# Yitran_IT900_Hutschiene_1_7.net
KiCad netlist of a schematic drawn in EAGLE
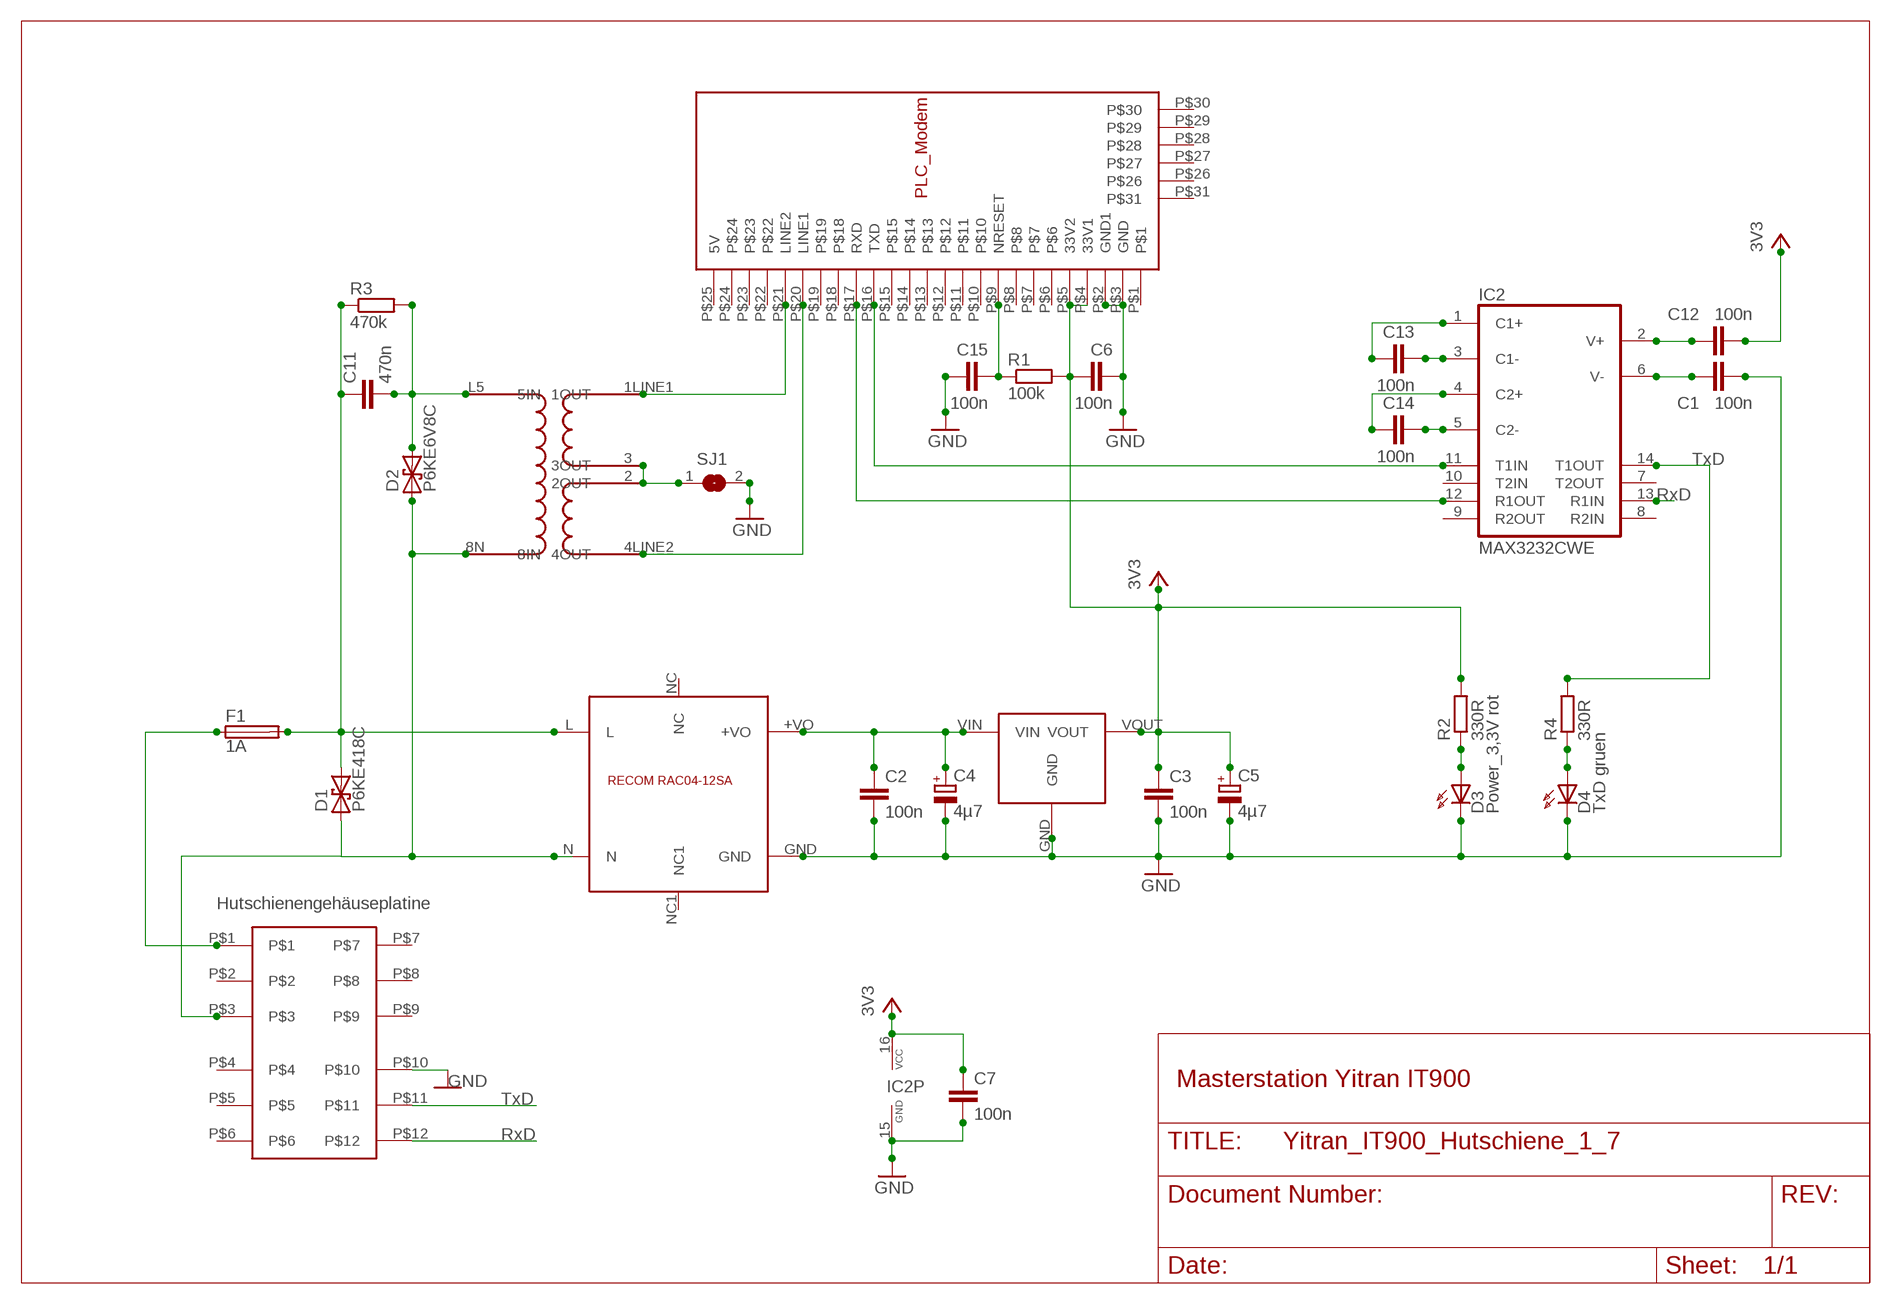
[diagram p0: schematic, sheet 1]

(export (version "E")
  (design (tool "Eeschema 10.0.6"))
  (components
    (comp (ref "C1")
      (value "100n")
      (footprint "eagle-import:C1206K")
      (libsource (lib "eagle-import") (part "C-EUC1206K"))
    )
    (comp (ref "C2")
      (value "100n")
      (footprint "eagle-import:C1206K")
      (libsource (lib "eagle-import") (part "C-EUC1206K"))
    )
    (comp (ref "C3")
      (value "100n")
      (footprint "eagle-import:C1206K")
      (libsource (lib "eagle-import") (part "C-EUC1206K"))
    )
    (comp (ref "C4")
      (value "4µ7")
      (footprint "eagle-import:E2,5-5")
      (libsource (lib "eagle-import") (part "CPOL-EUE2.5-5"))
    )
    (comp (ref "C5")
      (value "4µ7")
      (footprint "eagle-import:E2,5-5")
      (libsource (lib "eagle-import") (part "CPOL-EUE2.5-5"))
    )
    (comp (ref "C6")
      (value "100n")
      (footprint "eagle-import:C1206K")
      (libsource (lib "eagle-import") (part "C-EUC1206K"))
    )
    (comp (ref "C7")
      (value "100n")
      (footprint "eagle-import:C1206K")
      (libsource (lib "eagle-import") (part "C-EUC1206K"))
    )
    (comp (ref "C11")
      (value "470n")
      (footprint "eagle-import:C150-091X182")
      (libsource (lib "eagle-import") (part "C-EU150-091X182"))
    )
    (comp (ref "C12")
      (value "100n")
      (footprint "eagle-import:C1206K")
      (libsource (lib "eagle-import") (part "C-EUC1206K"))
    )
    (comp (ref "C13")
      (value "100n")
      (footprint "eagle-import:C1206K")
      (libsource (lib "eagle-import") (part "C-EUC1206K"))
    )
    (comp (ref "C14")
      (value "100n")
      (footprint "eagle-import:C1206K")
      (libsource (lib "eagle-import") (part "C-EUC1206K"))
    )
    (comp (ref "C15")
      (value "100n")
      (footprint "eagle-import:C1206K")
      (libsource (lib "eagle-import") (part "C-EUC1206K"))
    )
    (comp (ref "D1")
      (value "P6KE418C")
      (footprint "eagle-import:CB417-15")
      (libsource (lib "eagle-import") (part "P6KEXXC"))
    )
    (comp (ref "D2")
      (value "P6KE6V8C")
      (footprint "eagle-import:CB417-15")
      (libsource (lib "eagle-import") (part "P6KEXXC"))
    )
    (comp (ref "D3")
      (value "Power_3,3V rot")
      (footprint "eagle-import:HLMP6")
      (fields (field (name "MF") "AGILENT TECHNOLOGIES") (field (name "MPN") "HLMP-6500"))
      (libsource (lib "eagle-import") (part "HLMP6"))
    )
    (comp (ref "D4")
      (value "TxD gruen")
      (footprint "eagle-import:HLMP6")
      (fields (field (name "MF") "AGILENT TECHNOLOGIES") (field (name "MPN") "HLMP-6500"))
      (libsource (lib "eagle-import") (part "HLMP6"))
    )
    (comp (ref "F1")
      (value "1A")
      (footprint "eagle-import:TR5")
      (libsource (lib "eagle-import") (part "TR5"))
    )
    (comp (ref "IC2")
      (value "MAX3232CWE")
      (footprint "eagle-import:SO16L")
      (fields (field (name "MF") "MAXIM") (field (name "MPN") "MAX3232CWE+"))
      (libsource (lib "eagle-import") (part "MAX3232WEC"))
    )
    (comp (ref "R1")
      (value "100k")
      (footprint "eagle-import:M1406")
      (libsource (lib "eagle-import") (part "R-EU_M1406"))
    )
    (comp (ref "R2")
      (value "330R")
      (footprint "eagle-import:R1206")
      (libsource (lib "eagle-import") (part "R-EU_R1206"))
    )
    (comp (ref "R3")
      (value "470k")
      (footprint "eagle-import:0309_10")
      (libsource (lib "eagle-import") (part "R-EU_0309/10"))
    )
    (comp (ref "R4")
      (value "330R")
      (footprint "eagle-import:R1206")
      (libsource (lib "eagle-import") (part "R-EU_R1206"))
    )
    (comp (ref "SJ1")
      (value "SJW")
      (footprint "eagle-import:SJW")
      (libsource (lib "eagle-import") (part "SJW"))
    )
    (comp (ref "U$1")
      (value "RECOM_783_3")
      (footprint "eagle-import:RECOM785X")
      (libsource (lib "eagle-import") (part "RECOM_785_05"))
    )
    (comp (ref "U$2")
      (value "LDG-A-12")
      (footprint "eagle-import:LDG-A-12")
      (libsource (lib "eagle-import") (part "LDG-A-12"))
    )
    (comp (ref "U$3")
      (value "MODEMSTECKER")
      (footprint "eagle-import:MODEM_FUSS")
      (libsource (lib "eagle-import") (part "MODEMSTECKER"))
    )
    (comp (ref "U$9")
      (value "RECOM_RAC04_12SA")
      (footprint "eagle-import:RAC04_12SA")
      (libsource (lib "eagle-import") (part "RECOM_RAC04_12SA"))
    )
    (comp (ref "U$10")
      (value "PLC_UEBERTRAGER_V2")
      (footprint "eagle-import:PLC-UEBERTRAGER_V2")
      (libsource (lib "eagle-import") (part "PLC_UEBERTRAGER_V2"))
    )
  )
  (nets
    (net (code "1") (name "/RXD") (class "Default")
      (node (ref "IC2") (pin "13") (pinfunction "R1IN_13") (pintype "input"))
      (node (ref "U$2") (pin "P$12") (pinfunction "P$12_P$12") (pintype "bidirectional"))
    )
    (net (code "2") (name "/TXD") (class "Default")
      (node (ref "IC2") (pin "14") (pinfunction "T1OUT_14") (pintype "output"))
      (node (ref "R4") (pin "2") (pinfunction "2_2") (pintype "passive"))
      (node (ref "U$2") (pin "P$11") (pinfunction "P$11_P$11") (pintype "bidirectional"))
    )
    (net (code "3") (name "3V3") (class "Default")
      (node (ref "C12") (pin "2") (pinfunction "2_2") (pintype "passive"))
      (node (ref "C3") (pin "1") (pinfunction "1_1") (pintype "passive"))
      (node (ref "C5") (pin "+") (pinfunction "+_+") (pintype "passive"))
      (node (ref "C6") (pin "1") (pinfunction "1_1") (pintype "passive"))
      (node (ref "C7") (pin "1") (pinfunction "1_1") (pintype "passive"))
      (node (ref "IC2") (pin "16") (pinfunction "VCC_16") (pintype "power_in"))
      (node (ref "R1") (pin "2") (pinfunction "2_2") (pintype "passive"))
      (node (ref "R2") (pin "2") (pinfunction "2_2") (pintype "passive"))
      (node (ref "U$1") (pin "VOUT") (pinfunction "VOUT_VOUT") (pintype "bidirectional"))
      (node (ref "U$3") (pin "P$4") (pinfunction "33V1_P$4") (pintype "bidirectional"))
      (node (ref "U$3") (pin "P$5") (pinfunction "33V2_P$5") (pintype "bidirectional"))
    )
    (net (code "4") (name "GND") (class "Default")
      (node (ref "C1") (pin "2") (pinfunction "2_2") (pintype "passive"))
      (node (ref "C15") (pin "1") (pinfunction "1_1") (pintype "passive"))
      (node (ref "C2") (pin "2") (pinfunction "2_2") (pintype "passive"))
      (node (ref "C3") (pin "2") (pinfunction "2_2") (pintype "passive"))
      (node (ref "C4") (pin "-") (pinfunction "-_-") (pintype "passive"))
      (node (ref "C5") (pin "-") (pinfunction "-_-") (pintype "passive"))
      (node (ref "C6") (pin "2") (pinfunction "2_2") (pintype "passive"))
      (node (ref "C7") (pin "2") (pinfunction "2_2") (pintype "passive"))
      (node (ref "D3") (pin "K") (pinfunction "K_K") (pintype "passive"))
      (node (ref "D4") (pin "K") (pinfunction "K_K") (pintype "passive"))
      (node (ref "IC2") (pin "15") (pinfunction "GND_15") (pintype "power_in"))
      (node (ref "SJ1") (pin "2") (pinfunction "2_2") (pintype "passive"))
      (node (ref "U$1") (pin "GND") (pinfunction "GND_GND") (pintype "bidirectional"))
      (node (ref "U$2") (pin "P$10") (pinfunction "P$10_P$10") (pintype "bidirectional"))
      (node (ref "U$3") (pin "P$2") (pinfunction "GND1_P$2") (pintype "bidirectional"))
      (node (ref "U$3") (pin "P$3") (pinfunction "GND_P$3") (pintype "bidirectional"))
      (node (ref "U$9") (pin "GND") (pinfunction "GND_GND") (pintype "bidirectional"))
    )
    (net (code "5") (name "Net-(C2-Pad1)") (class "Default")
      (node (ref "C2") (pin "1") (pinfunction "1_1") (pintype "passive"))
      (node (ref "C4") (pin "+") (pinfunction "+_+") (pintype "passive"))
      (node (ref "U$1") (pin "VIN") (pinfunction "VIN_VIN") (pintype "bidirectional"))
      (node (ref "U$9") (pin "+VO") (pinfunction "+VO_+VO") (pintype "bidirectional"))
    )
    (net (code "6") (name "Net-(D1-1)") (class "Default")
      (node (ref "D1") (pin "A") (pinfunction "1_A") (pintype "passive"))
      (node (ref "D2") (pin "A") (pinfunction "1_A") (pintype "passive"))
      (node (ref "U$10") (pin "8N") (pinfunction "8IN_8N") (pintype "input"))
      (node (ref "U$2") (pin "P$3") (pinfunction "P$3_P$3") (pintype "bidirectional"))
      (node (ref "U$9") (pin "N") (pinfunction "N_N") (pintype "bidirectional"))
    )
    (net (code "7") (name "Net-(D1-2)") (class "Default")
      (node (ref "C11") (pin "1") (pinfunction "1_1") (pintype "passive"))
      (node (ref "D1") (pin "C") (pinfunction "2_C") (pintype "passive"))
      (node (ref "F1") (pin "2") (pinfunction "2_2") (pintype "passive"))
      (node (ref "R3") (pin "1") (pinfunction "1_1") (pintype "passive"))
      (node (ref "U$9") (pin "L") (pinfunction "L_L") (pintype "bidirectional"))
    )
    (net (code "8") (name "Net-(D2-2)") (class "Default")
      (node (ref "C11") (pin "2") (pinfunction "2_2") (pintype "passive"))
      (node (ref "D2") (pin "C") (pinfunction "2_C") (pintype "passive"))
      (node (ref "R3") (pin "2") (pinfunction "2_2") (pintype "passive"))
      (node (ref "U$10") (pin "L5") (pinfunction "5IN_L5") (pintype "input"))
    )
    (net (code "9") (name "Net-(D3-PadA)") (class "Default")
      (node (ref "D3") (pin "A") (pinfunction "A_A") (pintype "passive"))
      (node (ref "R2") (pin "1") (pinfunction "1_1") (pintype "passive"))
    )
    (net (code "10") (name "Net-(D4-PadA)") (class "Default")
      (node (ref "D4") (pin "A") (pinfunction "A_A") (pintype "passive"))
      (node (ref "R4") (pin "1") (pinfunction "1_1") (pintype "passive"))
    )
    (net (code "11") (name "Net-(F1-Pad1)") (class "Default")
      (node (ref "F1") (pin "1") (pinfunction "1_1") (pintype "passive"))
      (node (ref "U$2") (pin "P$1") (pinfunction "P$1_P$1") (pintype "bidirectional"))
    )
    (net (code "12") (name "Net-(IC2A-C1+)") (class "Default")
      (node (ref "C13") (pin "1") (pinfunction "1_1") (pintype "passive"))
      (node (ref "IC2") (pin "1") (pinfunction "C1+_1") (pintype "bidirectional"))
    )
    (net (code "13") (name "Net-(IC2A-C1-)") (class "Default")
      (node (ref "C13") (pin "2") (pinfunction "2_2") (pintype "passive"))
      (node (ref "IC2") (pin "3") (pinfunction "C1-_3") (pintype "bidirectional"))
    )
    (net (code "14") (name "Net-(IC2A-C2+)") (class "Default")
      (node (ref "C14") (pin "1") (pinfunction "1_1") (pintype "passive"))
      (node (ref "IC2") (pin "4") (pinfunction "C2+_4") (pintype "bidirectional"))
    )
    (net (code "15") (name "Net-(IC2A-C2-)") (class "Default")
      (node (ref "C14") (pin "2") (pinfunction "2_2") (pintype "passive"))
      (node (ref "IC2") (pin "5") (pinfunction "C2-_5") (pintype "bidirectional"))
    )
    (net (code "16") (name "Net-(IC2A-R1OUT)") (class "Default")
      (node (ref "IC2") (pin "12") (pinfunction "R1OUT_12") (pintype "output"))
      (node (ref "U$3") (pin "P$17") (pinfunction "RXD_P$17") (pintype "bidirectional"))
    )
    (net (code "17") (name "Net-(IC2A-T1IN)") (class "Default")
      (node (ref "IC2") (pin "11") (pinfunction "T1IN_11") (pintype "input"))
      (node (ref "U$3") (pin "P$16") (pinfunction "TXD_P$16") (pintype "bidirectional"))
    )
    (net (code "18") (name "Net-(IC2A-V+)") (class "Default")
      (node (ref "C12") (pin "1") (pinfunction "1_1") (pintype "passive"))
      (node (ref "IC2") (pin "2") (pinfunction "V+_2") (pintype "bidirectional"))
    )
    (net (code "19") (name "Net-(IC2A-V-)") (class "Default")
      (node (ref "C1") (pin "1") (pinfunction "1_1") (pintype "passive"))
      (node (ref "IC2") (pin "6") (pinfunction "V-_6") (pintype "bidirectional"))
    )
    (net (code "20") (name "Net-(U$3-NRESET)") (class "Default")
      (node (ref "C15") (pin "2") (pinfunction "2_2") (pintype "passive"))
      (node (ref "R1") (pin "1") (pinfunction "1_1") (pintype "passive"))
      (node (ref "U$3") (pin "P$9") (pinfunction "NRESET_P$9") (pintype "bidirectional"))
    )
    (net (code "21") (name "Net-(U$10-1OUT)") (class "Default")
      (node (ref "U$10") (pin "1LINE1") (pinfunction "1OUT_1LINE1") (pintype "output"))
      (node (ref "U$3") (pin "P$21") (pinfunction "LINE2_P$21") (pintype "bidirectional"))
    )
    (net (code "22") (name "Net-(U$10-2OUT)") (class "Default")
      (node (ref "SJ1") (pin "1") (pinfunction "1_1") (pintype "passive"))
      (node (ref "U$10") (pin "2") (pinfunction "2OUT_2") (pintype "output"))
      (node (ref "U$10") (pin "3") (pinfunction "3OUT_3") (pintype "output"))
    )
    (net (code "23") (name "Net-(U$10-4OUT)") (class "Default")
      (node (ref "U$10") (pin "4LINE2") (pinfunction "4OUT_4LINE2") (pintype "output"))
      (node (ref "U$3") (pin "P$20") (pinfunction "LINE1_P$20") (pintype "bidirectional"))
    )
    (net (code "24") (name "unconnected-(IC2A-R2IN-Pad8)") (class "Default")
      (node (ref "IC2") (pin "8") (pinfunction "R2IN_8") (pintype "input"))
    )
    (net (code "25") (name "unconnected-(IC2A-R2OUT-Pad9)") (class "Default")
      (node (ref "IC2") (pin "9") (pinfunction "R2OUT_9") (pintype "output"))
    )
    (net (code "26") (name "unconnected-(IC2A-T2IN-Pad10)") (class "Default")
      (node (ref "IC2") (pin "10") (pinfunction "T2IN_10") (pintype "input"))
    )
    (net (code "27") (name "unconnected-(IC2A-T2OUT-Pad7)") (class "Default")
      (node (ref "IC2") (pin "7") (pinfunction "T2OUT_7") (pintype "output"))
    )
    (net (code "28") (name "unconnected-(U$2-PadP$2)") (class "Default")
      (node (ref "U$2") (pin "P$2") (pinfunction "P$2_P$2") (pintype "bidirectional"))
    )
    (net (code "29") (name "unconnected-(U$2-PadP$4)") (class "Default")
      (node (ref "U$2") (pin "P$4") (pinfunction "P$4_P$4") (pintype "bidirectional"))
    )
    (net (code "30") (name "unconnected-(U$2-PadP$5)") (class "Default")
      (node (ref "U$2") (pin "P$5") (pinfunction "P$5_P$5") (pintype "bidirectional"))
    )
    (net (code "31") (name "unconnected-(U$2-PadP$6)") (class "Default")
      (node (ref "U$2") (pin "P$6") (pinfunction "P$6_P$6") (pintype "bidirectional"))
    )
    (net (code "32") (name "unconnected-(U$2-PadP$7)") (class "Default")
      (node (ref "U$2") (pin "P$7") (pinfunction "P$7_P$7") (pintype "bidirectional"))
    )
    (net (code "33") (name "unconnected-(U$2-PadP$8)") (class "Default")
      (node (ref "U$2") (pin "P$8") (pinfunction "P$8_P$8") (pintype "bidirectional"))
    )
    (net (code "34") (name "unconnected-(U$2-PadP$9)") (class "Default")
      (node (ref "U$2") (pin "P$9") (pinfunction "P$9_P$9") (pintype "bidirectional"))
    )
    (net (code "35") (name "unconnected-(U$3-5V-PadP$25)") (class "Default")
      (node (ref "U$3") (pin "P$25") (pinfunction "5V_P$25") (pintype "bidirectional"))
    )
    (net (code "36") (name "unconnected-(U$3-PadP$1)") (class "Default")
      (node (ref "U$3") (pin "P$1") (pinfunction "P$1_P$1") (pintype "bidirectional"))
    )
    (net (code "37") (name "unconnected-(U$3-PadP$6)") (class "Default")
      (node (ref "U$3") (pin "P$6") (pinfunction "P$6_P$6") (pintype "bidirectional"))
    )
    (net (code "38") (name "unconnected-(U$3-PadP$7)") (class "Default")
      (node (ref "U$3") (pin "P$7") (pinfunction "P$7_P$7") (pintype "bidirectional"))
    )
    (net (code "39") (name "unconnected-(U$3-PadP$8)") (class "Default")
      (node (ref "U$3") (pin "P$8") (pinfunction "P$8_P$8") (pintype "bidirectional"))
    )
    (net (code "40") (name "unconnected-(U$3-PadP$10)") (class "Default")
      (node (ref "U$3") (pin "P$10") (pinfunction "P$10_P$10") (pintype "bidirectional"))
    )
    (net (code "41") (name "unconnected-(U$3-PadP$11)") (class "Default")
      (node (ref "U$3") (pin "P$11") (pinfunction "P$11_P$11") (pintype "bidirectional"))
    )
    (net (code "42") (name "unconnected-(U$3-PadP$12)") (class "Default")
      (node (ref "U$3") (pin "P$12") (pinfunction "P$12_P$12") (pintype "bidirectional"))
    )
    (net (code "43") (name "unconnected-(U$3-PadP$13)") (class "Default")
      (node (ref "U$3") (pin "P$13") (pinfunction "P$13_P$13") (pintype "bidirectional"))
    )
    (net (code "44") (name "unconnected-(U$3-PadP$14)") (class "Default")
      (node (ref "U$3") (pin "P$14") (pinfunction "P$14_P$14") (pintype "bidirectional"))
    )
    (net (code "45") (name "unconnected-(U$3-PadP$15)") (class "Default")
      (node (ref "U$3") (pin "P$15") (pinfunction "P$15_P$15") (pintype "bidirectional"))
    )
    (net (code "46") (name "unconnected-(U$3-PadP$18)") (class "Default")
      (node (ref "U$3") (pin "P$18") (pinfunction "P$18_P$18") (pintype "bidirectional"))
    )
    (net (code "47") (name "unconnected-(U$3-PadP$19)") (class "Default")
      (node (ref "U$3") (pin "P$19") (pinfunction "P$19_P$19") (pintype "bidirectional"))
    )
    (net (code "48") (name "unconnected-(U$3-PadP$22)") (class "Default")
      (node (ref "U$3") (pin "P$22") (pinfunction "P$22_P$22") (pintype "bidirectional"))
    )
    (net (code "49") (name "unconnected-(U$3-PadP$23)") (class "Default")
      (node (ref "U$3") (pin "P$23") (pinfunction "P$23_P$23") (pintype "bidirectional"))
    )
    (net (code "50") (name "unconnected-(U$3-PadP$24)") (class "Default")
      (node (ref "U$3") (pin "P$24") (pinfunction "P$24_P$24") (pintype "bidirectional"))
    )
    (net (code "51") (name "unconnected-(U$3-PadP$26)") (class "Default")
      (node (ref "U$3") (pin "P$26") (pinfunction "P$26_P$26") (pintype "bidirectional"))
    )
    (net (code "52") (name "unconnected-(U$3-PadP$27)") (class "Default")
      (node (ref "U$3") (pin "P$27") (pinfunction "P$27_P$27") (pintype "bidirectional"))
    )
    (net (code "53") (name "unconnected-(U$3-PadP$28)") (class "Default")
      (node (ref "U$3") (pin "P$28") (pinfunction "P$28_P$28") (pintype "bidirectional"))
    )
    (net (code "54") (name "unconnected-(U$3-PadP$29)") (class "Default")
      (node (ref "U$3") (pin "P$29") (pinfunction "P$29_P$29") (pintype "bidirectional"))
    )
    (net (code "55") (name "unconnected-(U$3-PadP$30)") (class "Default")
      (node (ref "U$3") (pin "P$30") (pinfunction "P$30_P$30") (pintype "bidirectional"))
    )
    (net (code "56") (name "unconnected-(U$3-PadP$31)") (class "Default")
      (node (ref "U$3") (pin "P$31") (pinfunction "P$31_P$31") (pintype "bidirectional"))
    )
    (net (code "57") (name "unconnected-(U$9-PadNC)") (class "Default")
      (node (ref "U$9") (pin "NC") (pinfunction "NC_NC") (pintype "bidirectional"))
    )
    (net (code "58") (name "unconnected-(U$9-PadNC1)") (class "Default")
      (node (ref "U$9") (pin "NC1") (pinfunction "NC1_NC1") (pintype "bidirectional"))
    )
  )
)
